# Power.net
KiCad netlist of a schematic drawn in Altium Designer
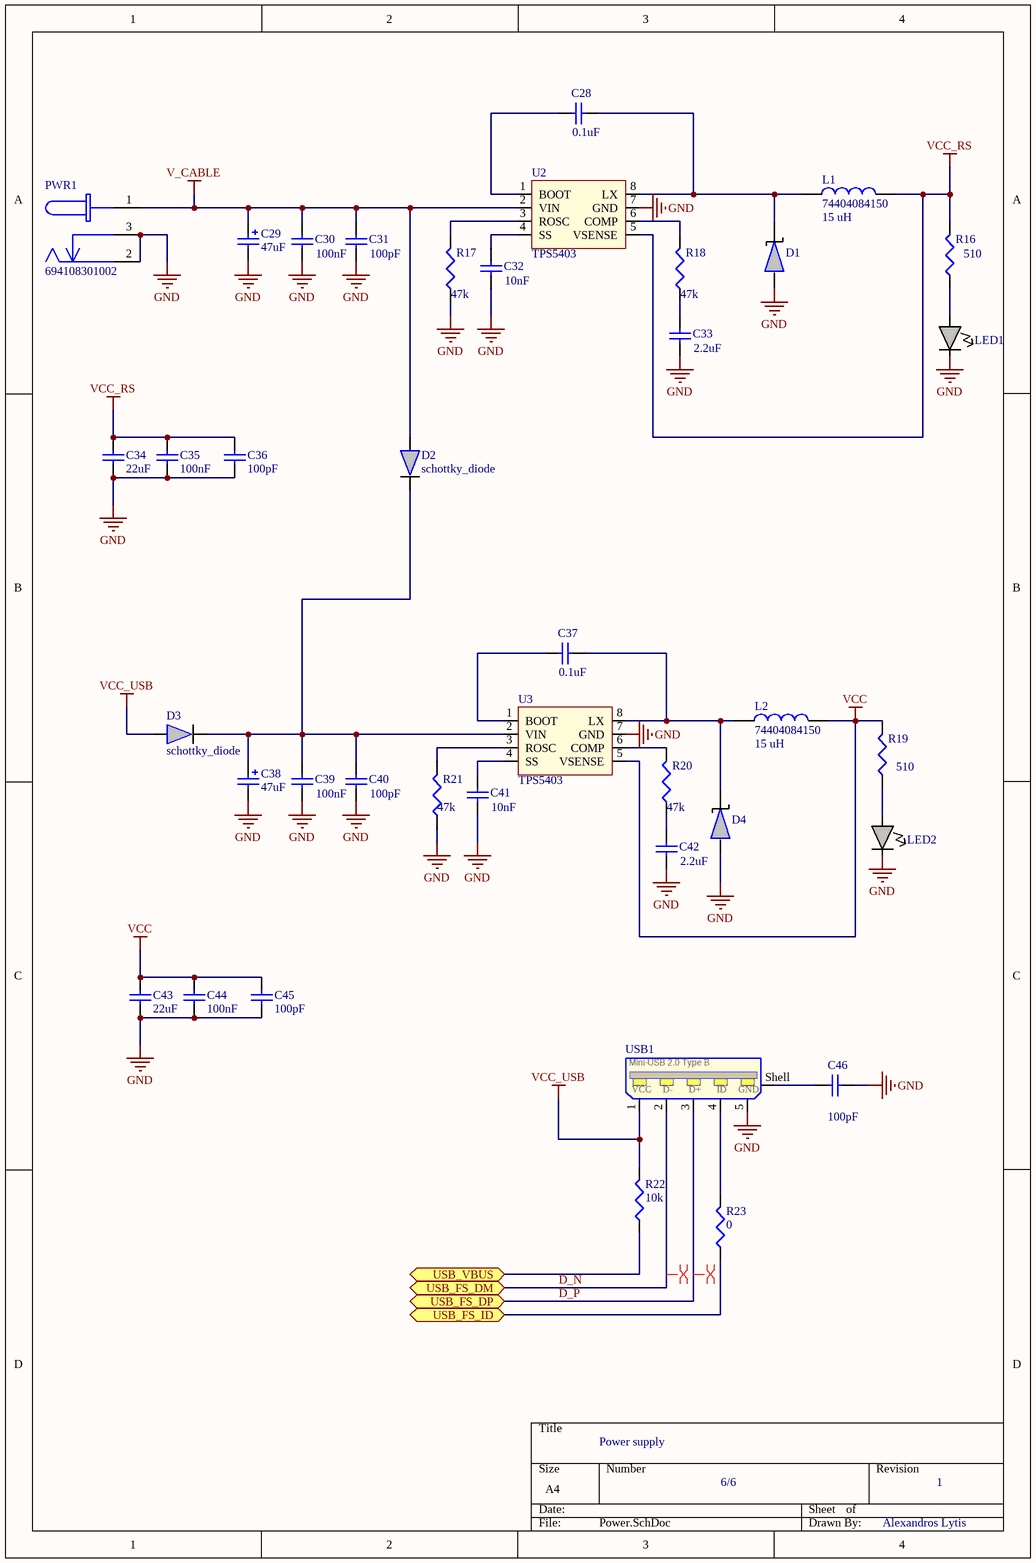
[diagram p0: Power.SchDoc]

(export (version "E")
  (design (tool "Eeschema 10.0.6"))
  (components
    (comp (ref "C28")
      (value "0.1uF")
      (footprint "CAP0603")
      (description "Capacitor (Semiconductor SIM Model)")
      (fields (field (name "Comment") "Cap Semi") (field (name "PUBLISHER") "Altium Limited"))
      (libsource (lib "Miscellaneous Devices") (part "Cap Semi"))
    )
    (comp (ref "C29")
      (value "47uF")
      (footprint "WCAP-ASLI_6.3x7.7")
      (description "WCAP-ASLI Aluminum Electrolytic Capacitors, 47uF")
      (fields (field (name "PARTNUMBER") "865080645012") (field (name "PUBLISHER") "Wurth Elektronik"))
      (libsource (lib "ALTIUM-WCAP-ASLI-rev16b") (part "WCAP-ASLI, 865080645012"))
    )
    (comp (ref "C30")
      (value "100nF")
      (footprint "CAP0603")
      (description "Capacitor (Semiconductor SIM Model)")
      (fields (field (name "Comment") "Cap Semi") (field (name "PUBLISHER") "Altium Limited"))
      (libsource (lib "Miscellaneous Devices") (part "Cap Semi"))
    )
    (comp (ref "C31")
      (value "100pF")
      (footprint "CAP0603")
      (description "Capacitor (Semiconductor SIM Model)")
      (fields (field (name "Comment") "Cap Semi") (field (name "PUBLISHER") "Altium Limited"))
      (libsource (lib "Miscellaneous Devices") (part "Cap Semi"))
    )
    (comp (ref "C32")
      (value "10nF")
      (footprint "CAP0603")
      (description "Capacitor (Semiconductor SIM Model)")
      (fields (field (name "Comment") "Cap Semi") (field (name "PUBLISHER") "Altium Limited"))
      (libsource (lib "Miscellaneous Devices") (part "Cap Semi"))
    )
    (comp (ref "C33")
      (value "2.2uF")
      (footprint "CAP0603")
      (description "Capacitor (Semiconductor SIM Model)")
      (fields (field (name "Comment") "Cap Semi") (field (name "PUBLISHER") "Altium Limited"))
      (libsource (lib "Miscellaneous Devices") (part "Cap Semi"))
    )
    (comp (ref "C34")
      (value "22uF")
      (footprint "WCAP-ASNP_6.3x5.5")
      (description "WCAP-ASNP Aluminum Electrolytic Capacitors, 22uF")
      (fields (field (name "PARTNUMBER") "865250543005") (field (name "PUBLISHER") "Wurth Elektronik"))
      (libsource (lib "ALTIUM-WCAP-ASNP-rev16a") (part "WCAP-ASNP, 865250543005"))
    )
    (comp (ref "C35")
      (value "100nF")
      (footprint "CAP0603")
      (description "Capacitor (Semiconductor SIM Model)")
      (fields (field (name "Comment") "Cap Semi") (field (name "PUBLISHER") "Altium Limited"))
      (libsource (lib "Miscellaneous Devices") (part "Cap Semi"))
    )
    (comp (ref "C36")
      (value "100pF")
      (footprint "CAP0603")
      (description "Capacitor (Semiconductor SIM Model)")
      (fields (field (name "Comment") "Cap Semi") (field (name "PUBLISHER") "Altium Limited"))
      (libsource (lib "Miscellaneous Devices") (part "Cap Semi"))
    )
    (comp (ref "C37")
      (value "0.1uF")
      (footprint "CAP0603")
      (description "Capacitor (Semiconductor SIM Model)")
      (fields (field (name "Comment") "Cap Semi") (field (name "PUBLISHER") "Altium Limited"))
      (libsource (lib "Miscellaneous Devices") (part "Cap Semi"))
    )
    (comp (ref "C38")
      (value "47uF")
      (footprint "WCAP-ASLI_6.3x7.7")
      (description "WCAP-ASLI Aluminum Electrolytic Capacitors, 47uF")
      (fields (field (name "PARTNUMBER") "865080645012") (field (name "PUBLISHER") "Wurth Elektronik"))
      (libsource (lib "ALTIUM-WCAP-ASLI-rev16b") (part "WCAP-ASLI, 865080645012"))
    )
    (comp (ref "C39")
      (value "100nF")
      (footprint "CAP0603")
      (description "Capacitor (Semiconductor SIM Model)")
      (fields (field (name "Comment") "Cap Semi") (field (name "PUBLISHER") "Altium Limited"))
      (libsource (lib "Miscellaneous Devices") (part "Cap Semi"))
    )
    (comp (ref "C40")
      (value "100pF")
      (footprint "CAP0603")
      (description "Capacitor (Semiconductor SIM Model)")
      (fields (field (name "Comment") "Cap Semi") (field (name "PUBLISHER") "Altium Limited"))
      (libsource (lib "Miscellaneous Devices") (part "Cap Semi"))
    )
    (comp (ref "C41")
      (value "10nF")
      (footprint "CAP0603")
      (description "Capacitor (Semiconductor SIM Model)")
      (fields (field (name "Comment") "Cap Semi") (field (name "PUBLISHER") "Altium Limited"))
      (libsource (lib "Miscellaneous Devices") (part "Cap Semi"))
    )
    (comp (ref "C42")
      (value "2.2uF")
      (footprint "CAP0603")
      (description "Capacitor (Semiconductor SIM Model)")
      (fields (field (name "Comment") "Cap Semi") (field (name "PUBLISHER") "Altium Limited"))
      (libsource (lib "Miscellaneous Devices") (part "Cap Semi"))
    )
    (comp (ref "C43")
      (value "22uF")
      (footprint "WCAP-ASNP_6.3x5.5")
      (description "WCAP-ASNP Aluminum Electrolytic Capacitors, 22uF")
      (fields (field (name "PARTNUMBER") "865250543005") (field (name "PUBLISHER") "Wurth Elektronik"))
      (libsource (lib "ALTIUM-WCAP-ASNP-rev16a") (part "WCAP-ASNP, 865250543005"))
    )
    (comp (ref "C44")
      (value "100nF")
      (footprint "CAP0603")
      (description "Capacitor (Semiconductor SIM Model)")
      (fields (field (name "Comment") "Cap Semi") (field (name "PUBLISHER") "Altium Limited"))
      (libsource (lib "Miscellaneous Devices") (part "Cap Semi"))
    )
    (comp (ref "C45")
      (value "100pF")
      (footprint "CAP0603")
      (description "Capacitor (Semiconductor SIM Model)")
      (fields (field (name "Comment") "Cap Semi") (field (name "PUBLISHER") "Altium Limited"))
      (libsource (lib "Miscellaneous Devices") (part "Cap Semi"))
    )
    (comp (ref "C46")
      (value "100pF")
      (footprint "CAP0603")
      (description "Capacitor (Semiconductor SIM Model)")
      (fields (field (name "Comment") "Cap Semi") (field (name "PUBLISHER") "Altium Limited"))
      (libsource (lib "Miscellaneous Devices") (part "Cap Semi"))
    )
    (comp (ref "D1")
      (value "schottky Diode")
      (footprint "DIOM1709X08N")
      (libsource (lib "Custom_Libraries") (part "SMD_schottky_CDBU0130L"))
    )
    (comp (ref "D2")
      (value "schottky_diode")
      (footprint "MBR180S1")
      (libsource (lib "Custom_Libraries") (part "MRB180S1 schottky"))
    )
    (comp (ref "D3")
      (value "schottky_diode")
      (footprint "MBR180S1")
      (libsource (lib "Custom_Libraries") (part "MRB180S1 schottky"))
    )
    (comp (ref "D4")
      (value "schottky Diode")
      (footprint "DIOM1709X08N")
      (libsource (lib "Custom_Libraries") (part "SMD_schottky_CDBU0130L"))
    )
    (comp (ref "L1")
      (value "74404084150")
      (footprint "WE-LQS_8040")
      (description "WE-LQS SMD Power Inductor, size 8040, 15 uH")
      (fields (field (name "ALTIUM_VALUE") "15 uH") (field (name "PUBLISHER") "Wurth Elektronik"))
      (libsource (lib "ALTIUM-WE-LQS-rev16b") (part "74404084150"))
    )
    (comp (ref "L2")
      (value "74404084150")
      (footprint "WE-LQS_8040")
      (description "WE-LQS SMD Power Inductor, size 8040, 15 uH")
      (fields (field (name "ALTIUM_VALUE") "15 uH") (field (name "PUBLISHER") "Wurth Elektronik"))
      (libsource (lib "ALTIUM-WE-LQS-rev16b") (part "74404084150"))
    )
    (comp (ref "LED1")
      (value "LED_1.6x0.8mm")
      (footprint "1608[0603]")
      (libsource (lib "Custom_Libraries") (part "LED_1.6x0.8mm"))
    )
    (comp (ref "LED2")
      (value "LED_1.6x0.8mm")
      (footprint "1608[0603]")
      (libsource (lib "Custom_Libraries") (part "LED_1.6x0.8mm"))
    )
    (comp (ref "PWR1")
      (value "694108301002")
      (footprint "694108301002")
      (description "WR-DC DC Power Jack Right Angled(6.4)")
      (fields (field (name "PUBLISHER") "Wurth Elektronik"))
      (libsource (lib "ALTIUM-WR-DC_POWER_JACK_CONNECTORS-rev16b") (part "694108301002"))
    )
    (comp (ref "R16")
      (value "510")
      (footprint "RES0603")
      (description "Resistor")
      (fields (field (name "Comment") "Res3") (field (name "PUBLISHER") "Altium Limited"))
      (libsource (lib "Miscellaneous Devices") (part "Res3"))
    )
    (comp (ref "R17")
      (value "47k")
      (footprint "RES0603")
      (description "Resistor")
      (fields (field (name "Comment") "Res3") (field (name "PUBLISHER") "Altium Limited"))
      (libsource (lib "Miscellaneous Devices") (part "Res3"))
    )
    (comp (ref "R18")
      (value "47k")
      (footprint "RES0603")
      (description "Resistor")
      (fields (field (name "Comment") "Res3") (field (name "PUBLISHER") "Altium Limited"))
      (libsource (lib "Miscellaneous Devices") (part "Res3"))
    )
    (comp (ref "R19")
      (value "510")
      (footprint "RES0603")
      (description "Resistor")
      (fields (field (name "Comment") "Res3") (field (name "PUBLISHER") "Altium Limited"))
      (libsource (lib "Miscellaneous Devices") (part "Res3"))
    )
    (comp (ref "R20")
      (value "47k")
      (footprint "RES0603")
      (description "Resistor")
      (fields (field (name "Comment") "Res3") (field (name "PUBLISHER") "Altium Limited"))
      (libsource (lib "Miscellaneous Devices") (part "Res3"))
    )
    (comp (ref "R21")
      (value "47k")
      (footprint "RES0603")
      (description "Resistor")
      (fields (field (name "Comment") "Res3") (field (name "PUBLISHER") "Altium Limited"))
      (libsource (lib "Miscellaneous Devices") (part "Res3"))
    )
    (comp (ref "R22")
      (value "10k")
      (footprint "RES0603")
      (description "Resistor")
      (fields (field (name "Comment") "Res3") (field (name "PUBLISHER") "Altium Limited"))
      (libsource (lib "Miscellaneous Devices") (part "Res3"))
    )
    (comp (ref "R23")
      (value "0")
      (footprint "RES0603")
      (description "Resistor")
      (fields (field (name "Comment") "Res3") (field (name "PUBLISHER") "Altium Limited"))
      (libsource (lib "Miscellaneous Devices") (part "Res3"))
    )
    (comp (ref "U2")
      (value "TPS5403")
      (footprint "SOIC127P600X175-8M")
      (description "switching power-3.3V")
      (libsource (lib "Custom_Libraries") (part "TPS5403"))
    )
    (comp (ref "U3")
      (value "TPS5403")
      (footprint "SOIC127P600X175-8M")
      (description "switching power-3.3V")
      (libsource (lib "Custom_Libraries") (part "TPS5403"))
    )
    (comp (ref "USB1")
      (value "65100516121")
      (footprint "65100516121")
      (description "WR-COM Mini USB 2.0 Type B SMT Horizontal 5 Contacts")
      (fields (field (name "PUBLISHER") "Wurth Elektronik"))
      (libsource (lib "ALTIUM-WR-COM-rev16d") (part "65100516121"))
    )
  )
  (nets
    (net (code "1") (name "/D_N") (class "Default")
      (node (ref "USB1") (pin "2") (pinfunction "D-_2") (pintype "passive"))
    )
    (net (code "2") (name "/D_P") (class "Default")
      (node (ref "USB1") (pin "3") (pinfunction "D+_3") (pintype "passive"))
    )
    (net (code "3") (name "/USB_FS_ID") (class "Default")
      (node (ref "R23") (pin "1") (pinfunction "1_1") (pintype "passive"))
    )
    (net (code "4") (name "/USB_VBUS") (class "Default")
      (node (ref "R22") (pin "1") (pinfunction "1_1") (pintype "passive"))
    )
    (net (code "5") (name "GND") (class "Default")
      (node (ref "C29") (pin "2") (pinfunction "N_2") (pintype "passive"))
      (node (ref "C30") (pin "1") (pinfunction "1_1") (pintype "passive"))
      (node (ref "C31") (pin "1") (pinfunction "1_1") (pintype "passive"))
      (node (ref "C32") (pin "1") (pinfunction "1_1") (pintype "passive"))
      (node (ref "C33") (pin "1") (pinfunction "1_1") (pintype "passive"))
      (node (ref "C34") (pin "1") (pinfunction "1_1") (pintype "passive"))
      (node (ref "C35") (pin "1") (pinfunction "1_1") (pintype "passive"))
      (node (ref "C36") (pin "1") (pinfunction "1_1") (pintype "passive"))
      (node (ref "C38") (pin "2") (pinfunction "N_2") (pintype "passive"))
      (node (ref "C39") (pin "1") (pinfunction "1_1") (pintype "passive"))
      (node (ref "C40") (pin "1") (pinfunction "1_1") (pintype "passive"))
      (node (ref "C41") (pin "1") (pinfunction "1_1") (pintype "passive"))
      (node (ref "C42") (pin "1") (pinfunction "1_1") (pintype "passive"))
      (node (ref "C43") (pin "1") (pinfunction "1_1") (pintype "passive"))
      (node (ref "C44") (pin "1") (pinfunction "1_1") (pintype "passive"))
      (node (ref "C45") (pin "1") (pinfunction "1_1") (pintype "passive"))
      (node (ref "C46") (pin "2") (pinfunction "2_2") (pintype "passive"))
      (node (ref "D1") (pin "2") (pinfunction "anode_2") (pintype "passive"))
      (node (ref "D4") (pin "2") (pinfunction "anode_2") (pintype "passive"))
      (node (ref "LED1") (pin "2") (pintype "passive"))
      (node (ref "LED2") (pin "2") (pintype "passive"))
      (node (ref "PWR1") (pin "2") (pinfunction "2_2") (pintype "passive"))
      (node (ref "PWR1") (pin "3") (pinfunction "3_3") (pintype "passive"))
      (node (ref "R17") (pin "1") (pinfunction "1_1") (pintype "passive"))
      (node (ref "R21") (pin "1") (pinfunction "1_1") (pintype "passive"))
      (node (ref "U2") (pin "7") (pinfunction "GND_7") (pintype "passive"))
      (node (ref "U3") (pin "7") (pinfunction "GND_7") (pintype "passive"))
      (node (ref "USB1") (pin "5") (pinfunction "GND_5") (pintype "passive"))
    )
    (net (code "6") (name "Net-(C33-Pad2)") (class "Default")
      (node (ref "C33") (pin "2") (pinfunction "2_2") (pintype "passive"))
      (node (ref "R18") (pin "1") (pinfunction "1_1") (pintype "passive"))
    )
    (net (code "7") (name "Net-(C38-P)") (class "Default")
      (node (ref "C38") (pin "1") (pinfunction "P_1") (pintype "passive"))
      (node (ref "C39") (pin "2") (pinfunction "2_2") (pintype "passive"))
      (node (ref "C40") (pin "2") (pinfunction "2_2") (pintype "passive"))
      (node (ref "D2") (pin "1") (pinfunction "Cathode_1") (pintype "passive"))
      (node (ref "D3") (pin "1") (pinfunction "Cathode_1") (pintype "passive"))
      (node (ref "U3") (pin "2") (pinfunction "VIN_2") (pintype "passive"))
    )
    (net (code "8") (name "Net-(C42-Pad2)") (class "Default")
      (node (ref "C42") (pin "2") (pinfunction "2_2") (pintype "passive"))
      (node (ref "R20") (pin "1") (pinfunction "1_1") (pintype "passive"))
    )
    (net (code "9") (name "Net-(C46-Pad1)") (class "Default")
      (node (ref "C46") (pin "1") (pinfunction "1_1") (pintype "passive"))
      (node (ref "USB1") (pin "Shell") (pinfunction "Shell_Shell") (pintype "passive"))
    )
    (net (code "10") (name "Net-(D1-Cathode)") (class "Default")
      (node (ref "C28") (pin "1") (pinfunction "1_1") (pintype "passive"))
      (node (ref "D1") (pin "1") (pinfunction "Cathode_1") (pintype "passive"))
      (node (ref "L1") (pin "1") (pinfunction "1_1") (pintype "passive"))
      (node (ref "U2") (pin "8") (pinfunction "LX_8") (pintype "passive"))
    )
    (net (code "11") (name "Net-(D4-Cathode)") (class "Default")
      (node (ref "C37") (pin "1") (pinfunction "1_1") (pintype "passive"))
      (node (ref "D4") (pin "1") (pinfunction "Cathode_1") (pintype "passive"))
      (node (ref "L2") (pin "1") (pinfunction "1_1") (pintype "passive"))
      (node (ref "U3") (pin "8") (pinfunction "LX_8") (pintype "passive"))
    )
    (net (code "12") (name "Net-(LED1-Pad1)") (class "Default")
      (node (ref "LED1") (pin "1") (pintype "passive"))
      (node (ref "R16") (pin "1") (pinfunction "1_1") (pintype "passive"))
    )
    (net (code "13") (name "Net-(LED2-Pad1)") (class "Default")
      (node (ref "LED2") (pin "1") (pintype "passive"))
      (node (ref "R19") (pin "1") (pinfunction "1_1") (pintype "passive"))
    )
    (net (code "14") (name "Net-(U2-BOOT)") (class "Default")
      (node (ref "C28") (pin "2") (pinfunction "2_2") (pintype "passive"))
      (node (ref "U2") (pin "1") (pinfunction "BOOT_1") (pintype "passive"))
    )
    (net (code "15") (name "Net-(U2-COMP)") (class "Default")
      (node (ref "R18") (pin "2") (pinfunction "2_2") (pintype "passive"))
      (node (ref "U2") (pin "6") (pinfunction "COMP_6") (pintype "passive"))
    )
    (net (code "16") (name "Net-(U2-ROSC)") (class "Default")
      (node (ref "R17") (pin "2") (pinfunction "2_2") (pintype "passive"))
      (node (ref "U2") (pin "3") (pinfunction "ROSC_3") (pintype "passive"))
    )
    (net (code "17") (name "Net-(U2-SS)") (class "Default")
      (node (ref "C32") (pin "2") (pinfunction "2_2") (pintype "passive"))
      (node (ref "U2") (pin "4") (pinfunction "SS_4") (pintype "passive"))
    )
    (net (code "18") (name "Net-(U3-BOOT)") (class "Default")
      (node (ref "C37") (pin "2") (pinfunction "2_2") (pintype "passive"))
      (node (ref "U3") (pin "1") (pinfunction "BOOT_1") (pintype "passive"))
    )
    (net (code "19") (name "Net-(U3-COMP)") (class "Default")
      (node (ref "R20") (pin "2") (pinfunction "2_2") (pintype "passive"))
      (node (ref "U3") (pin "6") (pinfunction "COMP_6") (pintype "passive"))
    )
    (net (code "20") (name "Net-(U3-ROSC)") (class "Default")
      (node (ref "R21") (pin "2") (pinfunction "2_2") (pintype "passive"))
      (node (ref "U3") (pin "3") (pinfunction "ROSC_3") (pintype "passive"))
    )
    (net (code "21") (name "Net-(U3-SS)") (class "Default")
      (node (ref "C41") (pin "2") (pinfunction "2_2") (pintype "passive"))
      (node (ref "U3") (pin "4") (pinfunction "SS_4") (pintype "passive"))
    )
    (net (code "22") (name "Net-(USB1-ID)") (class "Default")
      (node (ref "R23") (pin "2") (pinfunction "2_2") (pintype "passive"))
      (node (ref "USB1") (pin "4") (pinfunction "ID_4") (pintype "passive"))
    )
    (net (code "23") (name "VCC") (class "Default")
      (node (ref "C43") (pin "2") (pinfunction "2_2") (pintype "passive"))
      (node (ref "C44") (pin "2") (pinfunction "2_2") (pintype "passive"))
      (node (ref "C45") (pin "2") (pinfunction "2_2") (pintype "passive"))
      (node (ref "L2") (pin "2") (pinfunction "2_2") (pintype "passive"))
      (node (ref "R19") (pin "2") (pinfunction "2_2") (pintype "passive"))
      (node (ref "U3") (pin "5") (pinfunction "VSENSE_5") (pintype "passive"))
    )
    (net (code "24") (name "VCC_RS") (class "Default")
      (node (ref "C34") (pin "2") (pinfunction "2_2") (pintype "passive"))
      (node (ref "C35") (pin "2") (pinfunction "2_2") (pintype "passive"))
      (node (ref "C36") (pin "2") (pinfunction "2_2") (pintype "passive"))
      (node (ref "L1") (pin "2") (pinfunction "2_2") (pintype "passive"))
      (node (ref "R16") (pin "2") (pinfunction "2_2") (pintype "passive"))
      (node (ref "U2") (pin "5") (pinfunction "VSENSE_5") (pintype "passive"))
    )
    (net (code "25") (name "VCC_USB") (class "Default")
      (node (ref "D3") (pin "2") (pinfunction "Anode_2") (pintype "passive"))
      (node (ref "R22") (pin "2") (pinfunction "2_2") (pintype "passive"))
      (node (ref "USB1") (pin "1") (pinfunction "VCC_1") (pintype "passive"))
    )
    (net (code "26") (name "V_CABLE") (class "Default")
      (node (ref "C29") (pin "1") (pinfunction "P_1") (pintype "passive"))
      (node (ref "C30") (pin "2") (pinfunction "2_2") (pintype "passive"))
      (node (ref "C31") (pin "2") (pinfunction "2_2") (pintype "passive"))
      (node (ref "D2") (pin "2") (pinfunction "Anode_2") (pintype "passive"))
      (node (ref "PWR1") (pin "1") (pinfunction "1_1") (pintype "passive"))
      (node (ref "U2") (pin "2") (pinfunction "VIN_2") (pintype "passive"))
    )
  )
)
